# design.net
KiCad netlist of a schematic drawn in Altium Designer
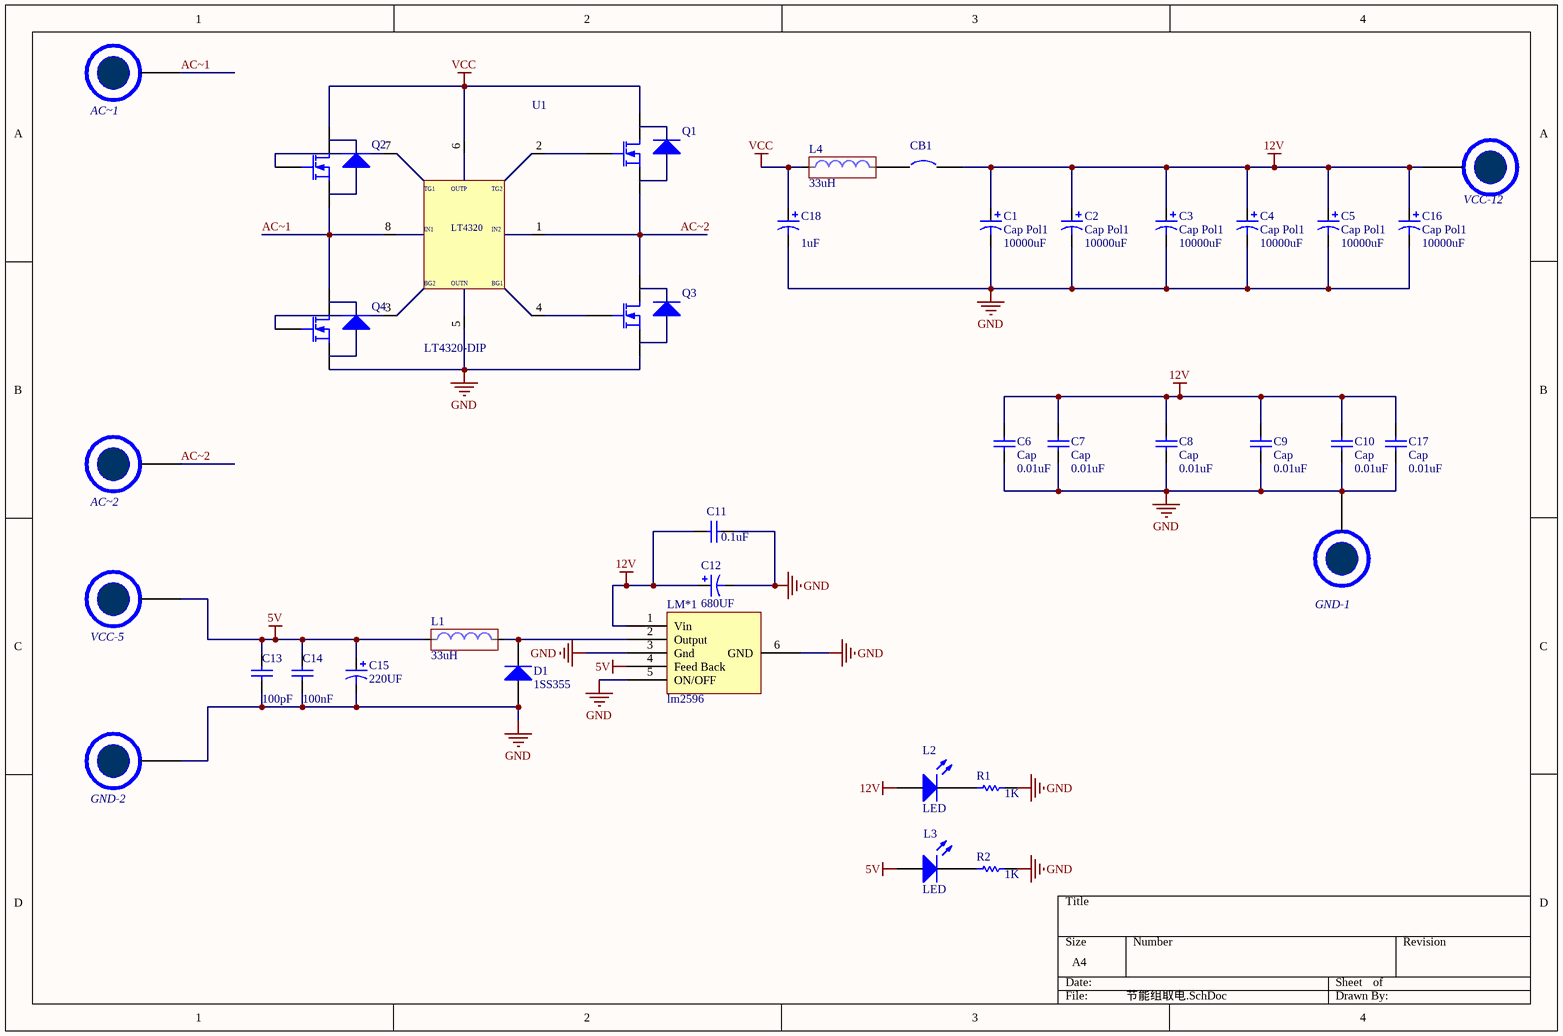
[diagram p0: 节能组取电.SchDoc]

(export (version "E")
  (design (tool "Eeschema 10.0.6"))
  (components
    (comp (ref "AC~1") (value "PIN") (footprint "PIN") (libsource (lib "常用元件库") (part "PIN")))
    (comp (ref "AC~2") (value "PIN") (footprint "PIN") (libsource (lib "常用元件库") (part "PIN")))
    (comp (ref "C1")
      (value "Cap Pol1")
      (footprint "RB7.6-15")
      (description "Polarized Capacitor (Radial)")
      (fields (field (name "ALTIUM_VALUE") "10000uF") (field (name "PUBLISHER") "Altium Limited"))
      (libsource (lib "Miscellaneous Devices") (part "Cap Pol1"))
    )
    (comp (ref "C2")
      (value "Cap Pol1")
      (footprint "RB7.6-15")
      (description "Polarized Capacitor (Radial)")
      (fields (field (name "ALTIUM_VALUE") "10000uF") (field (name "PUBLISHER") "Altium Limited"))
      (libsource (lib "Miscellaneous Devices") (part "Cap Pol1"))
    )
    (comp (ref "C3")
      (value "Cap Pol1")
      (footprint "RB7.6-15")
      (description "Polarized Capacitor (Radial)")
      (fields (field (name "ALTIUM_VALUE") "10000uF") (field (name "PUBLISHER") "Altium Limited"))
      (libsource (lib "Miscellaneous Devices") (part "Cap Pol1"))
    )
    (comp (ref "C4")
      (value "Cap Pol1")
      (footprint "RB7.6-15")
      (description "Polarized Capacitor (Radial)")
      (fields (field (name "ALTIUM_VALUE") "10000uF") (field (name "PUBLISHER") "Altium Limited"))
      (libsource (lib "Miscellaneous Devices") (part "Cap Pol1"))
    )
    (comp (ref "C5")
      (value "Cap Pol1")
      (footprint "RB7.6-15")
      (description "Polarized Capacitor (Radial)")
      (fields (field (name "ALTIUM_VALUE") "10000uF") (field (name "PUBLISHER") "Altium Limited"))
      (libsource (lib "Miscellaneous Devices") (part "Cap Pol1"))
    )
    (comp (ref "C6")
      (value "Cap")
      (footprint "C2012")
      (description "Capacitor")
      (fields (field (name "ALTIUM_VALUE") "0.01uF") (field (name "PUBLISHER") "Altium Limited"))
      (libsource (lib "Miscellaneous Devices") (part "Cap"))
    )
    (comp (ref "C7")
      (value "Cap")
      (footprint "C2012")
      (description "Capacitor")
      (fields (field (name "ALTIUM_VALUE") "0.01uF") (field (name "PUBLISHER") "Altium Limited"))
      (libsource (lib "Miscellaneous Devices") (part "Cap"))
    )
    (comp (ref "C8")
      (value "Cap")
      (footprint "C2012")
      (description "Capacitor")
      (fields (field (name "ALTIUM_VALUE") "0.01uF") (field (name "PUBLISHER") "Altium Limited"))
      (libsource (lib "Miscellaneous Devices") (part "Cap"))
    )
    (comp (ref "C9")
      (value "Cap")
      (footprint "C2012")
      (description "Capacitor")
      (fields (field (name "ALTIUM_VALUE") "0.01uF") (field (name "PUBLISHER") "Altium Limited"))
      (libsource (lib "Miscellaneous Devices") (part "Cap"))
    )
    (comp (ref "C10")
      (value "Cap")
      (footprint "C2012")
      (description "Capacitor")
      (fields (field (name "ALTIUM_VALUE") "0.01uF") (field (name "PUBLISHER") "Altium Limited"))
      (libsource (lib "Miscellaneous Devices") (part "Cap"))
    )
    (comp (ref "C11")
      (value "0.1uF")
      (footprint "C2012")
      (description "Capacitor")
      (fields (field (name "Comment") "Cap") (field (name "PUBLISHER") "Altium Limited"))
      (libsource (lib "Miscellaneous Devices") (part "Cap"))
    )
    (comp (ref "C12") (value "680UF") (footprint "c2012") (libsource (lib "电赛") (part "CAP+")))
    (comp (ref "C13")
      (value "100pF")
      (footprint "C2012")
      (description "Capacitor")
      (fields (field (name "Comment") "Cap") (field (name "PUBLISHER") "Altium Limited"))
      (libsource (lib "Miscellaneous Devices") (part "Cap"))
    )
    (comp (ref "C14")
      (value "100nF")
      (footprint "C2012")
      (description "Capacitor")
      (fields (field (name "Comment") "Cap") (field (name "PUBLISHER") "Altium Limited"))
      (libsource (lib "Miscellaneous Devices") (part "Cap"))
    )
    (comp (ref "C15") (value "220UF") (footprint "SMD-EC-F8") (libsource (lib "电赛") (part "CAP+")))
    (comp (ref "C16")
      (value "Cap Pol1")
      (footprint "RB7.6-15")
      (description "Polarized Capacitor (Radial)")
      (fields (field (name "ALTIUM_VALUE") "10000uF") (field (name "PUBLISHER") "Altium Limited"))
      (libsource (lib "Miscellaneous Devices") (part "Cap Pol1"))
    )
    (comp (ref "C17")
      (value "Cap")
      (footprint "C2012")
      (description "Capacitor")
      (fields (field (name "ALTIUM_VALUE") "0.01uF") (field (name "PUBLISHER") "Altium Limited"))
      (libsource (lib "Miscellaneous Devices") (part "Cap"))
    )
    (comp (ref "C18")
      (value "1uF")
      (footprint "C2012")
      (description "Polarized Capacitor (Radial)")
      (fields (field (name "Comment") "Cap Pol1") (field (name "PUBLISHER") "Altium Limited"))
      (libsource (lib "Miscellaneous Devices") (part "Cap Pol1"))
    )
    (comp (ref "CB1")
      (value "Circuit Breaker")
      (footprint "SPST-2")
      (fields (field (name "PUBLISHER") "Altium Limited"))
      (libsource (lib "Miscellaneous Devices") (part "Circuit Breaker"))
    )
    (comp (ref "D1")
      (value "1SS355")
      (footprint "SK54")
      (description "High Conductance Fast Diode")
      (fields (field (name "PUBLISHER") "Altium Limited"))
      (libsource (lib "K60-V4.0") (part "Diode 1N4148"))
    )
    (comp (ref "GND-1") (value "PIN") (footprint "PIN") (libsource (lib "常用元件库") (part "PIN")))
    (comp (ref "GND-2") (value "PIN") (footprint "PIN") (libsource (lib "常用元件库") (part "PIN")))
    (comp (ref "L1")
      (value "33uH")
      (footprint "SMD-EC-F6.3")
      (description "Inductor")
      (libsource (lib "Landzo") (part "Inductor"))
    )
    (comp (ref "L2") (value "LED") (footprint "C2012") (libsource (lib "Sparks") (part "LED")))
    (comp (ref "L3") (value "LED") (footprint "C2012") (libsource (lib "Sparks") (part "LED")))
    (comp (ref "L4")
      (value "33uH")
      (footprint "SMD-EC-F6.3")
      (description "Inductor")
      (libsource (lib "Landzo") (part "Inductor"))
    )
    (comp (ref "LM*1") (value "lm2596") (footprint "lm2596") (libsource (lib "2号库") (part "lm2596")))
    (comp (ref "Q1")
      (value "MOSFET-N")
      (footprint "mos")
      (description "N-Channel MOSFET")
      (fields (field (name "PUBLISHER") "Altium Limited"))
      (libsource (lib "原理图") (part "MOSFET-N"))
    )
    (comp (ref "Q2")
      (value "MOSFET-N")
      (footprint "mos")
      (description "N-Channel MOSFET")
      (fields (field (name "PUBLISHER") "Altium Limited"))
      (libsource (lib "原理图") (part "MOSFET-N"))
    )
    (comp (ref "Q3")
      (value "MOSFET-N")
      (footprint "mos")
      (description "N-Channel MOSFET")
      (fields (field (name "PUBLISHER") "Altium Limited"))
      (libsource (lib "原理图") (part "MOSFET-N"))
    )
    (comp (ref "Q4")
      (value "MOSFET-N")
      (footprint "mos")
      (description "N-Channel MOSFET")
      (fields (field (name "PUBLISHER") "Altium Limited"))
      (libsource (lib "原理图") (part "MOSFET-N"))
    )
    (comp (ref "R1")
      (value "1K")
      (footprint "R2012")
      (description "贴片电阻")
      (fields (field (name "Comment") "Res") (field (name "PUBLISHER") "Altium Limited"))
      (libsource (lib "Sparks") (part "Res"))
    )
    (comp (ref "R2")
      (value "1K")
      (footprint "R2012")
      (description "贴片电阻")
      (fields (field (name "Comment") "Res") (field (name "PUBLISHER") "Altium Limited"))
      (libsource (lib "Sparks") (part "Res"))
    )
    (comp (ref "U1") (value "LT4320-DIP") (footprint "DIP-8") (libsource (lib "2号库") (part "LT4320-DIP")))
    (comp (ref "VCC-5") (value "PIN") (footprint "PIN") (libsource (lib "常用元件库") (part "PIN")))
    (comp (ref "VCC-12") (value "PIN") (footprint "PIN") (libsource (lib "常用元件库") (part "PIN")))
  )
  (nets
    (net (code "1") (name "/AC~1") (class "Default")
      (node (ref "AC~1") (pin "1") (pinfunction "PIN_1") (pintype "passive"))
      (node (ref "Q2") (pin "3") (pinfunction "S_3") (pintype "passive"))
      (node (ref "Q4") (pin "2") (pinfunction "D_2") (pintype "passive"))
      (node (ref "U1") (pin "8") (pinfunction "8_8") (pintype "passive"))
    )
    (net (code "2") (name "/AC~2") (class "Default")
      (node (ref "AC~2") (pin "1") (pinfunction "PIN_1") (pintype "passive"))
      (node (ref "Q1") (pin "3") (pinfunction "S_3") (pintype "passive"))
      (node (ref "Q3") (pin "2") (pinfunction "D_2") (pintype "passive"))
      (node (ref "U1") (pin "1") (pinfunction "1_1") (pintype "passive"))
    )
    (net (code "3") (name "5V") (class "Default")
      (node (ref "C13") (pin "2") (pinfunction "2_2") (pintype "passive"))
      (node (ref "C14") (pin "2") (pinfunction "2_2") (pintype "passive"))
      (node (ref "C15") (pin "1") (pinfunction "1_1") (pintype "passive"))
      (node (ref "L1") (pin "1") (pinfunction "1_1") (pintype "passive"))
      (node (ref "L3") (pin "1") (pinfunction "A_1") (pintype "passive"))
      (node (ref "LM*1") (pin "4") (pinfunction "Feed_Back_4") (pintype "passive"))
      (node (ref "VCC-5") (pin "1") (pinfunction "PIN_1") (pintype "passive"))
    )
    (net (code "4") (name "12V") (class "Default")
      (node (ref "C1") (pin "1") (pinfunction "1_1") (pintype "passive"))
      (node (ref "C10") (pin "2") (pinfunction "2_2") (pintype "passive"))
      (node (ref "C11") (pin "2") (pinfunction "2_2") (pintype "passive"))
      (node (ref "C12") (pin "1") (pinfunction "1_1") (pintype "passive"))
      (node (ref "C16") (pin "1") (pinfunction "1_1") (pintype "passive"))
      (node (ref "C17") (pin "2") (pinfunction "2_2") (pintype "passive"))
      (node (ref "C2") (pin "1") (pinfunction "1_1") (pintype "passive"))
      (node (ref "C3") (pin "1") (pinfunction "1_1") (pintype "passive"))
      (node (ref "C4") (pin "1") (pinfunction "1_1") (pintype "passive"))
      (node (ref "C5") (pin "1") (pinfunction "1_1") (pintype "passive"))
      (node (ref "C6") (pin "2") (pinfunction "2_2") (pintype "passive"))
      (node (ref "C7") (pin "2") (pinfunction "2_2") (pintype "passive"))
      (node (ref "C8") (pin "2") (pinfunction "2_2") (pintype "passive"))
      (node (ref "C9") (pin "2") (pinfunction "2_2") (pintype "passive"))
      (node (ref "CB1") (pin "2") (pinfunction "2_2") (pintype "passive"))
      (node (ref "L2") (pin "1") (pinfunction "A_1") (pintype "passive"))
      (node (ref "LM*1") (pin "1") (pinfunction "Vin_1") (pintype "passive"))
      (node (ref "VCC-12") (pin "1") (pinfunction "PIN_1") (pintype "passive"))
    )
    (net (code "5") (name "GND") (class "Default")
      (node (ref "C1") (pin "2") (pinfunction "2_2") (pintype "passive"))
      (node (ref "C10") (pin "1") (pinfunction "1_1") (pintype "passive"))
      (node (ref "C11") (pin "1") (pinfunction "1_1") (pintype "passive"))
      (node (ref "C12") (pin "2") (pinfunction "2_2") (pintype "passive"))
      (node (ref "C13") (pin "1") (pinfunction "1_1") (pintype "passive"))
      (node (ref "C14") (pin "1") (pinfunction "1_1") (pintype "passive"))
      (node (ref "C15") (pin "2") (pinfunction "2_2") (pintype "passive"))
      (node (ref "C16") (pin "2") (pinfunction "2_2") (pintype "passive"))
      (node (ref "C17") (pin "1") (pinfunction "1_1") (pintype "passive"))
      (node (ref "C18") (pin "2") (pinfunction "2_2") (pintype "passive"))
      (node (ref "C2") (pin "2") (pinfunction "2_2") (pintype "passive"))
      (node (ref "C3") (pin "2") (pinfunction "2_2") (pintype "passive"))
      (node (ref "C4") (pin "2") (pinfunction "2_2") (pintype "passive"))
      (node (ref "C5") (pin "2") (pinfunction "2_2") (pintype "passive"))
      (node (ref "C6") (pin "1") (pinfunction "1_1") (pintype "passive"))
      (node (ref "C7") (pin "1") (pinfunction "1_1") (pintype "passive"))
      (node (ref "C8") (pin "1") (pinfunction "1_1") (pintype "passive"))
      (node (ref "C9") (pin "1") (pinfunction "1_1") (pintype "passive"))
      (node (ref "D1") (pin "1") (pinfunction "A_1") (pintype "passive"))
      (node (ref "GND-1") (pin "1") (pinfunction "PIN_1") (pintype "passive"))
      (node (ref "GND-2") (pin "1") (pinfunction "PIN_1") (pintype "passive"))
      (node (ref "LM*1") (pin "3") (pinfunction "Gnd_3") (pintype "passive"))
      (node (ref "LM*1") (pin "5") (pinfunction "ON/OFF_5") (pintype "passive"))
      (node (ref "LM*1") (pin "6") (pinfunction "GND_6") (pintype "passive"))
      (node (ref "Q3") (pin "3") (pinfunction "S_3") (pintype "passive"))
      (node (ref "Q4") (pin "3") (pinfunction "S_3") (pintype "passive"))
      (node (ref "R1") (pin "2") (pinfunction "2_2") (pintype "passive"))
      (node (ref "R2") (pin "2") (pinfunction "2_2") (pintype "passive"))
      (node (ref "U1") (pin "5") (pinfunction "5_5") (pintype "passive"))
    )
    (net (code "6") (name "Net-(CB1-Pad1)") (class "Default")
      (node (ref "CB1") (pin "1") (pinfunction "1_1") (pintype "passive"))
      (node (ref "L4") (pin "2") (pinfunction "2_2") (pintype "passive"))
    )
    (net (code "7") (name "Net-(D1-K)") (class "Default")
      (node (ref "D1") (pin "2") (pinfunction "K_2") (pintype "passive"))
      (node (ref "L1") (pin "2") (pinfunction "2_2") (pintype "passive"))
      (node (ref "LM*1") (pin "2") (pinfunction "Output_2") (pintype "passive"))
    )
    (net (code "8") (name "Net-(L2-K)") (class "Default")
      (node (ref "L2") (pin "2") (pinfunction "K_2") (pintype "passive"))
      (node (ref "R1") (pin "1") (pinfunction "1_1") (pintype "passive"))
    )
    (net (code "9") (name "Net-(L3-K)") (class "Default")
      (node (ref "L3") (pin "2") (pinfunction "K_2") (pintype "passive"))
      (node (ref "R2") (pin "1") (pinfunction "1_1") (pintype "passive"))
    )
    (net (code "10") (name "Net-(Q1-G)") (class "Default")
      (node (ref "Q1") (pin "1") (pinfunction "G_1") (pintype "passive"))
      (node (ref "U1") (pin "2") (pinfunction "2_2") (pintype "passive"))
    )
    (net (code "11") (name "Net-(Q2-G)") (class "Default")
      (node (ref "Q2") (pin "1") (pinfunction "G_1") (pintype "passive"))
      (node (ref "U1") (pin "7") (pinfunction "7_7") (pintype "passive"))
    )
    (net (code "12") (name "Net-(Q3-G)") (class "Default")
      (node (ref "Q3") (pin "1") (pinfunction "G_1") (pintype "passive"))
      (node (ref "U1") (pin "4") (pinfunction "4_4") (pintype "passive"))
    )
    (net (code "13") (name "Net-(Q4-G)") (class "Default")
      (node (ref "Q4") (pin "1") (pinfunction "G_1") (pintype "passive"))
      (node (ref "U1") (pin "3") (pinfunction "3_3") (pintype "passive"))
    )
    (net (code "14") (name "VCC") (class "Default")
      (node (ref "C18") (pin "1") (pinfunction "1_1") (pintype "passive"))
      (node (ref "L4") (pin "1") (pinfunction "1_1") (pintype "passive"))
      (node (ref "Q1") (pin "2") (pinfunction "D_2") (pintype "passive"))
      (node (ref "Q2") (pin "2") (pinfunction "D_2") (pintype "passive"))
      (node (ref "U1") (pin "6") (pinfunction "6_6") (pintype "passive"))
    )
  )
)
